# Power_Selection_-_Power_Supply.net
KiCad netlist of a schematic drawn in Altium Designer
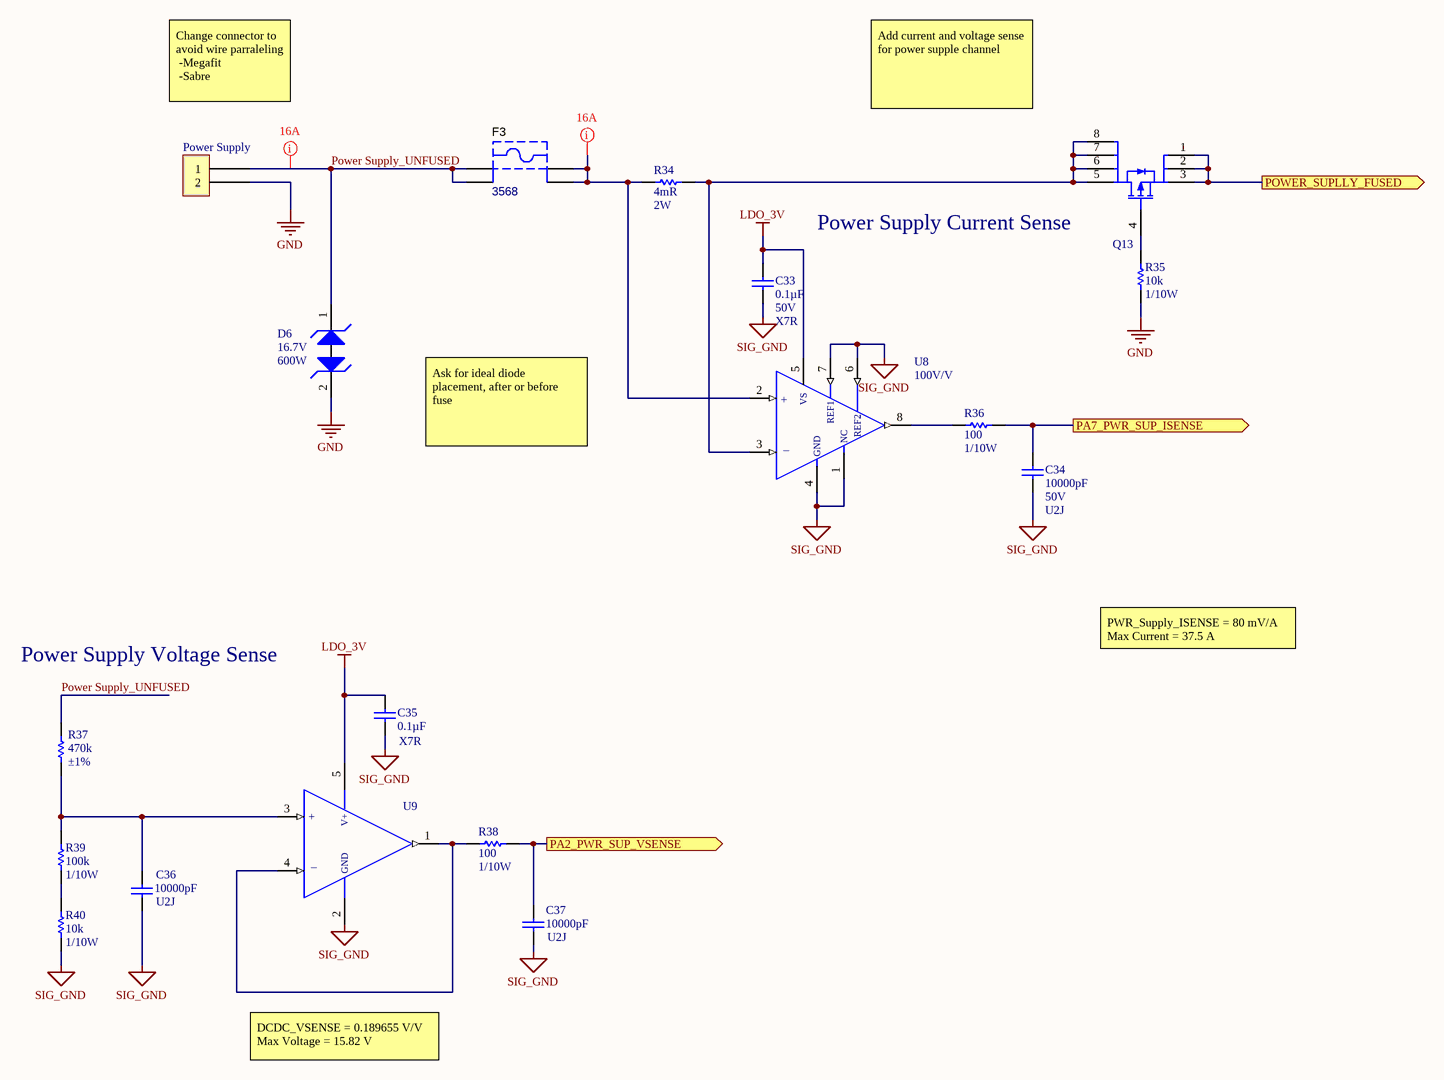
[diagram p0: Power Selection - Power Supply.SchDoc]

(export (version "E")
  (design (tool "Eeschema 10.0.6"))
  (components
    (comp (ref "C33")
      (value "CAP CER 0.1UF 50V 10% X7R 0603")
      (footprint "CAP, 0603")
      (description "0.10µF ±10% 50V Ceramic Capacitor X7R 0603 (1608 Metric)")
      (fields
        (field (name "TOLERANCE") "±10%")
        (field (name "CAPACITANCE") "0.1µF")
        (field (name "VOLTAGE") "50V")
        (field (name "TEMPERATURE COEFFICIENT") "X7R")
      )
      (libsource (lib "Schematic Diagrams") (part "CAP CER 0.1UF 50V 10% X7R 0603"))
    )
    (comp (ref "C34")
      (value "CAP CER 10nF 50V 5% X7R 0603")
      (footprint "CAP, 0603")
      (description "10000pF ±5% 50V Ceramic Capacitor U2J 0603 (1608 Metric)")
      (fields
        (field (name "TOLERANCE") "±5%")
        (field (name "CAPACITANCE") "10000pF")
        (field (name "VOLTAGE") "50V")
        (field (name "TEMPERATURE COEFFICIENT") "U2J")
      )
      (libsource (lib "Schematic Diagrams") (part "CAP CER 10nF 50V 5% X7R 0603"))
    )
    (comp (ref "C35")
      (value "CAP CER 0.1UF 50V 10% X7R 0603")
      (footprint "CAP, 0603")
      (description "0.10µF ±10% 50V Ceramic Capacitor X7R 0603 (1608 Metric)")
      (fields
        (field (name "TOLERANCE") "±10%")
        (field (name "CAPACITANCE") "0.1µF")
        (field (name "TEMPERATURE COEFFICIENT") "X7R")
        (field (name "VOLTAGE") "50V")
      )
      (libsource (lib "Schematic Diagrams") (part "CAP CER 0.1UF 50V 10% X7R 0603"))
    )
    (comp (ref "C36")
      (value "CAP CER 10nF 50V 5% X7R 0603")
      (footprint "CAP, 0603")
      (description "10000pF ±5% 50V Ceramic Capacitor U2J 0603 (1608 Metric)")
      (fields
        (field (name "TOLERANCE") "±5%")
        (field (name "CAPACITANCE") "10000pF")
        (field (name "TEMPERATURE COEFFICIENT") "U2J")
        (field (name "VOLTAGE") "50V")
      )
      (libsource (lib "Schematic Diagrams") (part "CAP CER 10nF 50V 5% X7R 0603"))
    )
    (comp (ref "C37")
      (value "CAP CER 10nF 50V 5% X7R 0603")
      (footprint "CAP, 0603")
      (description "10000pF ±5% 50V Ceramic Capacitor U2J 0603 (1608 Metric)")
      (fields
        (field (name "TOLERANCE") "±5%")
        (field (name "CAPACITANCE") "10000pF")
        (field (name "TEMPERATURE COEFFICIENT") "U2J")
        (field (name "VOLTAGE") "50V")
      )
      (libsource (lib "Schematic Diagrams") (part "CAP CER 10nF 50V 5% X7R 0603"))
    )
    (comp (ref "D6")
      (value "DIODE TVS 15VWM 24.4VC DO-214AA (SMB)")
      (footprint "DO-214AA Diode")
      (description "TVS DIODE 15VWM 24.4VC SMB")
      (fields (field (name "VOLTAGE - BREAKDOWN (MIN)") "16.7V") (field (name "POWER - PEAK PULSE") "600W"))
      (libsource (lib "Schematic Diagrams") (part "DIODE TVS 15VWM 24.4VC DO-214AA (SMB)"))
    )
    (comp (ref "F3")
      (value "3568")
      (footprint "KSTN-3568_V")
      (description "Fuse Holder 20A 500VAC Pin Through Hole")
      (fields (field (name "VOLTAGE") "500V"))
      (libsource (lib "University of Waterloo - Solar Car Team") (part "FUSE_HOLDER-4"))
    )
    (comp (ref "Power Supply")
      (value "CONN HEADER TE  ELCON Mini 2POS PCB")
      (footprint "CONN HEADER TE  ELCON Mini 2POS PCB-Footprint-1")
      (description "CONN HEADER 2POS PCB")
      (libsource (lib "University of Waterloo - Solar Car Team") (part "CONN HEADER TE  ELCON Mini 2POS PCB"))
    )
    (comp (ref "Q13")
      (value "MOSFET P-CH PWR56 40V 4.9 MOHM")
      (footprint "PMOS PWR56 40V 4.9 MOHM")
      (description "P-Channel 16V 2.5A (Ta) 650mW (Ta) Surface Mount X2-DFN2015-3")
      (libsource (lib "Schematic Diagrams") (part "MOSFET P-CH PWR56 40V 4.9 MOHM"))
    )
    (comp (ref "R34")
      (value "RES 4m OHM 1% 2W 2010")
      (footprint "RES 2010")
      (description "4 mOhms ±1% 2W Chip Resistor 2010 (5025 Metric) Automotive AEC-Q200, Current Sense Metal Element")
      (fields (field (name "RESISTANCE") "4mR") (field (name "POWER (WATTS)") "2W"))
      (libsource (lib "Schematic Diagrams") (part "RES 4m OHM 1% 2W 2010"))
    )
    (comp (ref "R35")
      (value "RES 10K OHM 1% 1/10W 0603")
      (footprint "RES, 0603")
      (description "RES SMD 10K OHM 1% 1/10W 0603")
      (fields
        (field (name "TOLERANCE") "±1%")
        (field (name "RESISTANCE") "10k")
        (field (name "POWER") "1/10W")
      )
      (libsource (lib "Schematic Diagrams") (part "RES 10K OHM 1% 1/10W 0603"))
    )
    (comp (ref "R36")
      (value "RES 100 OHM 1% 1/10W 0603")
      (footprint "RES, 0603")
      (description "100 Ohm ±1% 0.1W, 1/10W Chip Resistor 0603 (1608 Metric) Moisture Resistant Thick Film")
      (fields
        (field (name "TOLERANCE") "±1%")
        (field (name "RESISTANCE") "100")
        (field (name "POWER") "1/10W")
      )
      (libsource (lib "Schematic Diagrams") (part "RES 100 OHM 1% 1/10W 0603"))
    )
    (comp (ref "R37")
      (value "RES 470K OHM 1% 1/4W 0603")
      (footprint "RES, 0603")
      (description "RES SMD 470K OHM 1% 1/4W 0603")
      (fields (field (name "RESISTANCE") "470k") (field (name "TOLERANCE") "±1%"))
      (libsource (lib "Schematic Diagrams") (part "RES 470K OHM 1% 1/4W 0603"))
    )
    (comp (ref "R38")
      (value "RES 100 OHM 1% 1/10W 0603")
      (footprint "RES, 0603")
      (description "100 Ohm ±1% 0.1W, 1/10W Chip Resistor 0603 (1608 Metric) Moisture Resistant Thick Film")
      (fields
        (field (name "TOLERANCE") "±1%")
        (field (name "RESISTANCE") "100")
        (field (name "POWER") "1/10W")
      )
      (libsource (lib "Schematic Diagrams") (part "RES 100 OHM 1% 1/10W 0603"))
    )
    (comp (ref "R39")
      (value "RES 100K OHM 5% 1/8W 0603")
      (footprint "RES, 0603")
      (description "RES SMD 100K OHM 5% 1/10W 0603")
      (fields
        (field (name "TOLERANCE") "±5%")
        (field (name "RESISTANCE") "100k")
        (field (name "POWER") "1/10W")
      )
      (libsource (lib "Schematic Diagrams") (part "RES 100K OHM 5% 1/8W 0603"))
    )
    (comp (ref "R40")
      (value "RES 10K OHM 1% 1/10W 0603")
      (footprint "RES, 0603")
      (description "RES SMD 10K OHM 1% 1/10W 0603")
      (fields
        (field (name "TOLERANCE") "±1%")
        (field (name "RESISTANCE") "10k")
        (field (name "POWER") "1/10W")
      )
      (libsource (lib "Schematic Diagrams") (part "RES 10K OHM 1% 1/10W 0603"))
    )
    (comp (ref "U8")
      (value "100V/V")
      (footprint "IC CURRENT AMPLIFIER INA240 TSSOP-8")
      (description "Current Sense Amplifier 1 Circuit 8-TSSOP")
      (libsource (lib "Schematic Diagrams") (part "IC CURRENT AMPLIFIER INA240 8-TSSOP"))
    )
    (comp (ref "U9")
      (value "IC OP AMP GEN PURPOSE RR 10MHZ SOT-23-5")
      (footprint "IC OP AMP GP RR 10MHZ SOT-23-5")
      (description "General Purpose Amplifier 1 Circuit Rail-to-Rail SOT-23-5")
      (libsource (lib "Schematic Diagrams") (part "IC OP AMP GEN PURPOSE RR 10MHZ SOT-23-5"))
    )
  )
  (nets
    (net (code "1") (name "/PA2_PWR_SUP_VSENSE") (class "Default")
      (node (ref "C37") (pin "1") (pinfunction "1_1") (pintype "passive"))
      (node (ref "R38") (pin "2") (pinfunction "2_2") (pintype "passive"))
    )
    (net (code "2") (name "/PA7_PWR_SUP_ISENSE") (class "Default")
      (node (ref "C34") (pin "1") (pinfunction "1_1") (pintype "passive"))
      (node (ref "R36") (pin "2") (pinfunction "2_2") (pintype "passive"))
    )
    (net (code "3") (name "/POWER_SUPLLY_FUSED") (class "Default")
      (node (ref "Q13") (pin "1") (pinfunction "S_1") (pintype "passive"))
      (node (ref "Q13") (pin "2") (pinfunction "S_2") (pintype "passive"))
      (node (ref "Q13") (pin "3") (pinfunction "S_3") (pintype "passive"))
    )
    (net (code "4") (name "/Power Supply_UNFUSED") (class "Default")
      (node (ref "D6") (pin "1") (pinfunction "Cathode1_1") (pintype "passive"))
      (node (ref "F3") (pin "1") (pinfunction "1_1") (pintype "passive"))
      (node (ref "F3") (pin "2") (pinfunction "2_2") (pintype "passive"))
      (node (ref "Power Supply") (pin "1") (pinfunction "1_1") (pintype "passive"))
      (node (ref "R37") (pin "1") (pinfunction "1_1") (pintype "passive"))
    )
    (net (code "5") (name "GND") (class "Default")
      (node (ref "D6") (pin "2") (pinfunction "Cathode2_2") (pintype "passive"))
      (node (ref "Power Supply") (pin "2") (pinfunction "2_2") (pintype "passive"))
      (node (ref "R35") (pin "2") (pinfunction "2_2") (pintype "passive"))
    )
    (net (code "6") (name "LDO_3V") (class "Default")
      (node (ref "C33") (pin "1") (pinfunction "1_1") (pintype "passive"))
      (node (ref "C35") (pin "1") (pinfunction "1_1") (pintype "passive"))
      (node (ref "U8") (pin "5") (pinfunction "VS_5") (pintype "power_in"))
      (node (ref "U9") (pin "5") (pinfunction "VDD_5") (pintype "power_in"))
    )
    (net (code "7") (name "Net-(Q13-G)") (class "Default")
      (node (ref "Q13") (pin "4") (pinfunction "G_4") (pintype "passive"))
      (node (ref "R35") (pin "1") (pinfunction "1_1") (pintype "passive"))
    )
    (net (code "8") (name "Net-(R39-Pad2)") (class "Default")
      (node (ref "R39") (pin "2") (pinfunction "2_2") (pintype "passive"))
      (node (ref "R40") (pin "1") (pinfunction "1_1") (pintype "passive"))
    )
    (net (code "9") (name "Net-(U8-+IN)") (class "Default")
      (node (ref "F3") (pin "3") (pinfunction "3_3") (pintype "passive"))
      (node (ref "F3") (pin "4") (pinfunction "4_4") (pintype "passive"))
      (node (ref "R34") (pin "1") (pinfunction "1_1") (pintype "passive"))
      (node (ref "U8") (pin "2") (pinfunction "+IN_2") (pintype "input"))
    )
    (net (code "10") (name "Net-(U8--IN)") (class "Default")
      (node (ref "Q13") (pin "5") (pinfunction "D_5") (pintype "passive"))
      (node (ref "Q13") (pin "6") (pinfunction "D_6") (pintype "passive"))
      (node (ref "Q13") (pin "7") (pinfunction "D_7") (pintype "passive"))
      (node (ref "Q13") (pin "8") (pinfunction "D_8") (pintype "passive"))
      (node (ref "R34") (pin "2") (pinfunction "2_2") (pintype "passive"))
      (node (ref "U8") (pin "3") (pinfunction "-IN_3") (pintype "input"))
    )
    (net (code "11") (name "Net-(U8-OUTPUT)") (class "Default")
      (node (ref "R36") (pin "1") (pinfunction "1_1") (pintype "passive"))
      (node (ref "U8") (pin "8") (pinfunction "OUTPUT_8") (pintype "output"))
    )
    (net (code "12") (name "Net-(U9-+IN)") (class "Default")
      (node (ref "C36") (pin "1") (pinfunction "1_1") (pintype "passive"))
      (node (ref "R37") (pin "2") (pinfunction "2_2") (pintype "passive"))
      (node (ref "R39") (pin "1") (pinfunction "1_1") (pintype "passive"))
      (node (ref "U9") (pin "3") (pinfunction "+IN_3") (pintype "input"))
    )
    (net (code "13") (name "Net-(U9--IN)") (class "Default")
      (node (ref "R38") (pin "1") (pinfunction "1_1") (pintype "passive"))
      (node (ref "U9") (pin "1") (pinfunction "OUTPUT_1") (pintype "output"))
      (node (ref "U9") (pin "4") (pinfunction "-IN_4") (pintype "input"))
    )
    (net (code "14") (name "SIG_GND") (class "Default")
      (node (ref "C33") (pin "2") (pinfunction "2_2") (pintype "passive"))
      (node (ref "C34") (pin "2") (pinfunction "2_2") (pintype "passive"))
      (node (ref "C35") (pin "2") (pinfunction "2_2") (pintype "passive"))
      (node (ref "C36") (pin "2") (pinfunction "2_2") (pintype "passive"))
      (node (ref "C37") (pin "2") (pinfunction "2_2") (pintype "passive"))
      (node (ref "R40") (pin "2") (pinfunction "2_2") (pintype "passive"))
      (node (ref "U8") (pin "1") (pinfunction "NC_1") (pintype "power_in"))
      (node (ref "U8") (pin "4") (pinfunction "GND_4") (pintype "power_in"))
      (node (ref "U8") (pin "6") (pinfunction "REF2_6") (pintype "input"))
      (node (ref "U8") (pin "7") (pinfunction "REF1_7") (pintype "input"))
      (node (ref "U9") (pin "2") (pinfunction "VSS_2") (pintype "power_in"))
    )
  )
)
